# PIC24FJ64GB002_BT.net
KiCad netlist of a schematic drawn in EAGLE
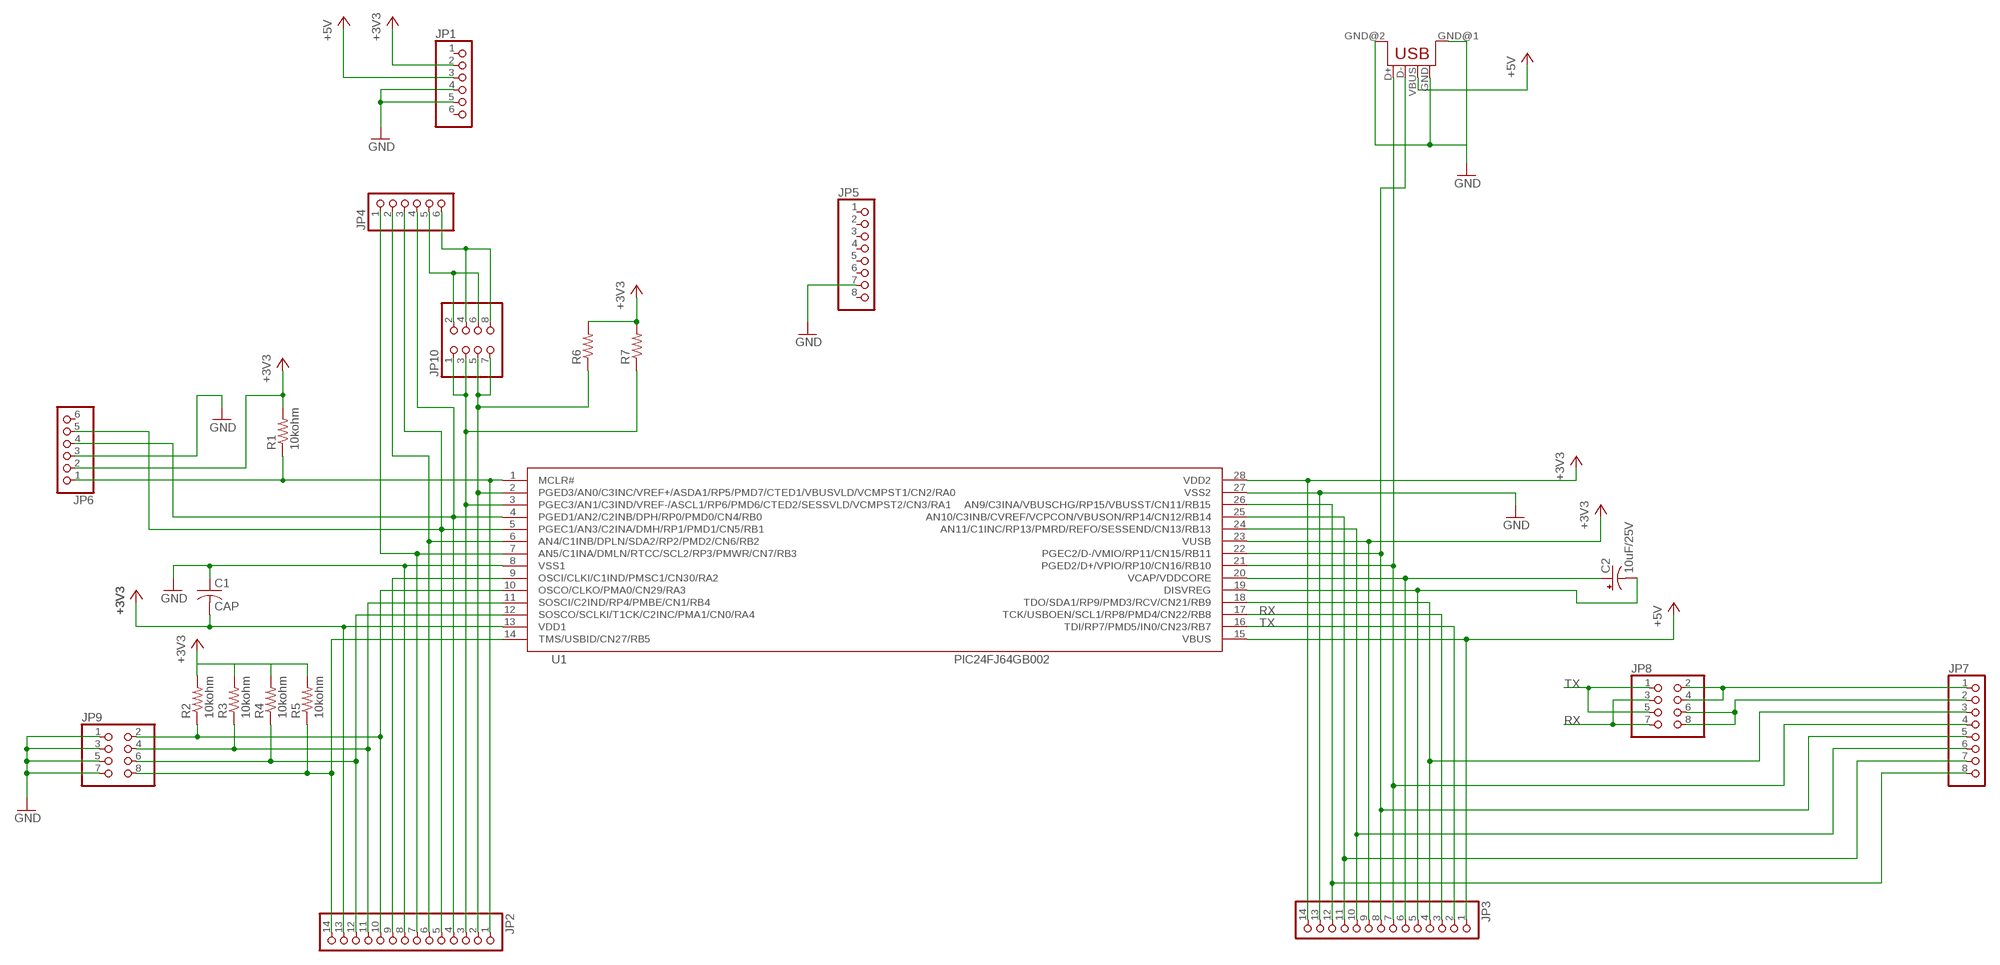
[diagram p0: schematic, sheet 1]

(export (version "E")
  (design (tool "Eeschema 10.0.6"))
  (components
    (comp (ref "C1")
      (value "CAP")
      (footprint "eagle-import:C025-040X050")
      (libsource (lib "eagle-import") (part "CAP"))
    )
    (comp (ref "C2")
      (value "10uF/25V")
      (footprint "eagle-import:CPOL-US")
      (libsource (lib "eagle-import") (part "CPOL-US"))
    )
    (comp (ref "CON1")
      (value "USB")
      (footprint "eagle-import:USB-FEMALE-A-PTH")
      (libsource (lib "eagle-import") (part "USB"))
    )
    (comp (ref "JP1")
      (value "PINHD-1X6")
      (footprint "eagle-import:1X06")
      (libsource (lib "eagle-import") (part "PINHD-1X6"))
    )
    (comp (ref "JP2")
      (value "PINHD-1X14")
      (footprint "eagle-import:1X14")
      (libsource (lib "eagle-import") (part "PINHD-1X14"))
    )
    (comp (ref "JP3")
      (value "PINHD-1X14")
      (footprint "eagle-import:1X14")
      (libsource (lib "eagle-import") (part "PINHD-1X14"))
    )
    (comp (ref "JP4")
      (value "PINHD-1X6")
      (footprint "eagle-import:1X06")
      (libsource (lib "eagle-import") (part "PINHD-1X6"))
    )
    (comp (ref "JP5")
      (value "PINHD-1X8")
      (footprint "eagle-import:1X08")
      (libsource (lib "eagle-import") (part "PINHD-1X8"))
    )
    (comp (ref "JP6")
      (value "PINHD-1X6")
      (footprint "eagle-import:1X06")
      (libsource (lib "eagle-import") (part "PINHD-1X6"))
    )
    (comp (ref "JP7")
      (value "PINHD-1X8")
      (footprint "eagle-import:1X08")
      (libsource (lib "eagle-import") (part "PINHD-1X8"))
    )
    (comp (ref "JP8")
      (value "PINHD-2X4")
      (footprint "eagle-import:2X04")
      (libsource (lib "eagle-import") (part "PINHD-2X4"))
    )
    (comp (ref "JP9")
      (value "PINHD-2X4")
      (footprint "eagle-import:2X04")
      (libsource (lib "eagle-import") (part "PINHD-2X4"))
    )
    (comp (ref "JP10")
      (value "PINHD-2X4")
      (footprint "eagle-import:2X04")
      (libsource (lib "eagle-import") (part "PINHD-2X4"))
    )
    (comp (ref "R1")
      (value "10kohm")
      (footprint "eagle-import:0204V")
      (libsource (lib "eagle-import") (part "R-US-01"))
    )
    (comp (ref "R2")
      (value "10kohm")
      (footprint "eagle-import:0204V")
      (libsource (lib "eagle-import") (part "R-US-01"))
    )
    (comp (ref "R3")
      (value "10kohm")
      (footprint "eagle-import:0204V")
      (libsource (lib "eagle-import") (part "R-US-01"))
    )
    (comp (ref "R4")
      (value "10kohm")
      (footprint "eagle-import:0204V")
      (libsource (lib "eagle-import") (part "R-US-01"))
    )
    (comp (ref "R5")
      (value "10kohm")
      (footprint "eagle-import:0204V")
      (libsource (lib "eagle-import") (part "R-US-01"))
    )
    (comp (ref "R6")
      (value "R-US-01")
      (footprint "eagle-import:0204V")
      (libsource (lib "eagle-import") (part "R-US-01"))
    )
    (comp (ref "R7")
      (value "R-US-01")
      (footprint "eagle-import:0204V")
      (libsource (lib "eagle-import") (part "R-US-01"))
    )
    (comp (ref "U1")
      (value "PIC24FJ64GB002")
      (footprint "eagle-import:DIP28")
      (libsource (lib "eagle-import") (part "PIC24FJ64GB002"))
    )
  )
  (nets
    (net (code "1") (name "+3V3") (class "Default")
      (node (ref "C1") (pin "2") (pinfunction "2_2") (pintype "passive"))
      (node (ref "JP1") (pin "2") (pinfunction "2_2") (pintype "passive"))
      (node (ref "JP2") (pin "13") (pinfunction "13_13") (pintype "passive"))
      (node (ref "JP3") (pin "14") (pinfunction "14_14") (pintype "passive"))
      (node (ref "JP3") (pin "9") (pinfunction "9_9") (pintype "passive"))
      (node (ref "JP6") (pin "2") (pinfunction "2_2") (pintype "passive"))
      (node (ref "R1") (pin "2") (pinfunction "2_2") (pintype "passive"))
      (node (ref "R2") (pin "2") (pinfunction "2_2") (pintype "passive"))
      (node (ref "R3") (pin "2") (pinfunction "2_2") (pintype "passive"))
      (node (ref "R4") (pin "2") (pinfunction "2_2") (pintype "passive"))
      (node (ref "R5") (pin "2") (pinfunction "2_2") (pintype "passive"))
      (node (ref "R6") (pin "2") (pinfunction "2_2") (pintype "passive"))
      (node (ref "R7") (pin "2") (pinfunction "2_2") (pintype "passive"))
      (node (ref "U1") (pin "13") (pinfunction "VDD1_13") (pintype "power_in"))
      (node (ref "U1") (pin "23") (pinfunction "VUSB_23") (pintype "power_in"))
      (node (ref "U1") (pin "28") (pinfunction "VDD2_28") (pintype "power_in"))
    )
    (net (code "2") (name "+5V") (class "Default")
      (node (ref "CON1") (pin "VBUS") (pinfunction "VBUS_VBUS") (pintype "bidirectional"))
      (node (ref "JP1") (pin "3") (pinfunction "3_3") (pintype "passive"))
      (node (ref "JP3") (pin "1") (pinfunction "1_1") (pintype "passive"))
      (node (ref "U1") (pin "15") (pinfunction "VBUS_15") (pintype "power_in"))
    )
    (net (code "3") (name "/RX") (class "Default")
      (node (ref "JP3") (pin "3") (pinfunction "3_3") (pintype "passive"))
      (node (ref "JP8") (pin "3") (pinfunction "3_3") (pintype "passive"))
      (node (ref "JP8") (pin "7") (pinfunction "7_7") (pintype "passive"))
      (node (ref "U1") (pin "17") (pinfunction "TCK/USBOEN/SCL1/RP8/PMD4/CN22/RB8_17") (pintype "bidirectional"))
    )
    (net (code "4") (name "/TX") (class "Default")
      (node (ref "JP3") (pin "2") (pinfunction "2_2") (pintype "passive"))
      (node (ref "JP8") (pin "1") (pinfunction "1_1") (pintype "passive"))
      (node (ref "JP8") (pin "5") (pinfunction "5_5") (pintype "passive"))
      (node (ref "U1") (pin "16") (pinfunction "TDI/RP7/PMD5/IN0/CN23/RB7_16") (pintype "bidirectional"))
    )
    (net (code "5") (name "GND") (class "Default")
      (node (ref "C1") (pin "1") (pinfunction "1_1") (pintype "passive"))
      (node (ref "CON1") (pin "GND") (pinfunction "GND_GND") (pintype "bidirectional"))
      (node (ref "CON1") (pin "GND@1") (pinfunction "GND_GND@1") (pintype "bidirectional"))
      (node (ref "CON1") (pin "GND@2") (pinfunction "GND_GND@2") (pintype "bidirectional"))
      (node (ref "JP1") (pin "4") (pinfunction "4_4") (pintype "passive"))
      (node (ref "JP1") (pin "5") (pinfunction "5_5") (pintype "passive"))
      (node (ref "JP2") (pin "8") (pinfunction "8_8") (pintype "passive"))
      (node (ref "JP3") (pin "13") (pinfunction "13_13") (pintype "passive"))
      (node (ref "JP5") (pin "7") (pinfunction "7_7") (pintype "passive"))
      (node (ref "JP6") (pin "3") (pinfunction "3_3") (pintype "passive"))
      (node (ref "JP9") (pin "1") (pinfunction "1_1") (pintype "passive"))
      (node (ref "JP9") (pin "3") (pinfunction "3_3") (pintype "passive"))
      (node (ref "JP9") (pin "5") (pinfunction "5_5") (pintype "passive"))
      (node (ref "JP9") (pin "7") (pinfunction "7_7") (pintype "passive"))
      (node (ref "U1") (pin "27") (pinfunction "VSS2_27") (pintype "power_in"))
      (node (ref "U1") (pin "8") (pinfunction "VSS1_8") (pintype "power_in"))
    )
    (net (code "6") (name "Net-(JP7-Pad1)") (class "Default")
      (node (ref "JP7") (pin "1") (pinfunction "1_1") (pintype "passive"))
      (node (ref "JP8") (pin "2") (pinfunction "2_2") (pintype "passive"))
      (node (ref "JP8") (pin "4") (pinfunction "4_4") (pintype "passive"))
    )
    (net (code "7") (name "Net-(JP7-Pad2)") (class "Default")
      (node (ref "JP7") (pin "2") (pinfunction "2_2") (pintype "passive"))
      (node (ref "JP8") (pin "6") (pinfunction "6_6") (pintype "passive"))
      (node (ref "JP8") (pin "8") (pinfunction "8_8") (pintype "passive"))
    )
    (net (code "8") (name "Net-(JP10-Pad2)") (class "Default")
      (node (ref "JP10") (pin "2") (pinfunction "2_2") (pintype "passive"))
      (node (ref "JP10") (pin "6") (pinfunction "6_6") (pintype "passive"))
      (node (ref "JP4") (pin "5") (pinfunction "5_5") (pintype "passive"))
    )
    (net (code "9") (name "Net-(JP10-Pad4)") (class "Default")
      (node (ref "JP10") (pin "4") (pinfunction "4_4") (pintype "passive"))
      (node (ref "JP10") (pin "8") (pinfunction "8_8") (pintype "passive"))
      (node (ref "JP4") (pin "6") (pinfunction "6_6") (pintype "passive"))
    )
    (net (code "10") (name "Net-(U1-AN4{slash}C1INB{slash}DPLN{slash}SDA2{slash}RP2{slash}PMD2{slash}CN6{slash}RB2)") (class "Default")
      (node (ref "JP2") (pin "6") (pinfunction "6_6") (pintype "passive"))
      (node (ref "JP4") (pin "2") (pinfunction "2_2") (pintype "passive"))
      (node (ref "U1") (pin "6") (pinfunction "AN4/C1INB/DPLN/SDA2/RP2/PMD2/CN6/RB2_6") (pintype "bidirectional"))
    )
    (net (code "11") (name "Net-(U1-AN5{slash}C1INA{slash}DMLN{slash}RTCC{slash}SCL2{slash}RP3{slash}PMWR{slash}CN7{slash}RB3)") (class "Default")
      (node (ref "JP2") (pin "7") (pinfunction "7_7") (pintype "passive"))
      (node (ref "JP4") (pin "1") (pinfunction "1_1") (pintype "passive"))
      (node (ref "U1") (pin "7") (pinfunction "AN5/C1INA/DMLN/RTCC/SCL2/RP3/PMWR/CN7/RB3_7") (pintype "bidirectional"))
    )
    (net (code "12") (name "Net-(U1-AN9{slash}C3INA{slash}VBUSCHG{slash}RP15{slash}VBUSST{slash}CN11{slash}RB15)") (class "Default")
      (node (ref "JP3") (pin "12") (pinfunction "12_12") (pintype "passive"))
      (node (ref "JP7") (pin "8") (pinfunction "8_8") (pintype "passive"))
      (node (ref "U1") (pin "26") (pinfunction "AN9/C3INA/VBUSCHG/RP15/VBUSST/CN11/RB15_26") (pintype "bidirectional"))
    )
    (net (code "13") (name "Net-(U1-AN10{slash}C3INB{slash}CVREF{slash}VCPCON{slash}VBUSON{slash}RP14{slash}CN12{slash}RB14)") (class "Default")
      (node (ref "JP3") (pin "11") (pinfunction "11_11") (pintype "passive"))
      (node (ref "JP7") (pin "7") (pinfunction "7_7") (pintype "passive"))
      (node (ref "U1") (pin "25") (pinfunction "AN10/C3INB/CVREF/VCPCON/VBUSON/RP14/CN12/RB14_25") (pintype "bidirectional"))
    )
    (net (code "14") (name "Net-(U1-AN11{slash}C1INC{slash}RP13{slash}PMRD{slash}REFO{slash}SESSEND{slash}CN13{slash}RB13)") (class "Default")
      (node (ref "JP3") (pin "10") (pinfunction "10_10") (pintype "passive"))
      (node (ref "JP7") (pin "6") (pinfunction "6_6") (pintype "passive"))
      (node (ref "U1") (pin "24") (pinfunction "AN11/C1INC/RP13/PMRD/REFO/SESSEND/CN13/RB13_24") (pintype "bidirectional"))
    )
    (net (code "15") (name "Net-(U1-DISVREG)") (class "Default")
      (node (ref "C2") (pin "-") (pinfunction "-_-") (pintype "passive"))
      (node (ref "JP3") (pin "5") (pinfunction "5_5") (pintype "passive"))
      (node (ref "U1") (pin "19") (pinfunction "DISVREG_19") (pintype "power_in"))
    )
    (net (code "16") (name "Net-(U1-MCLR#)") (class "Default")
      (node (ref "JP2") (pin "1") (pinfunction "1_1") (pintype "passive"))
      (node (ref "JP6") (pin "1") (pinfunction "1_1") (pintype "passive"))
      (node (ref "R1") (pin "1") (pinfunction "1_1") (pintype "passive"))
      (node (ref "U1") (pin "1") (pinfunction "MCLR#_1") (pintype "bidirectional"))
    )
    (net (code "17") (name "Net-(U1-OSCI{slash}CLKI{slash}C1IND{slash}PMSC1{slash}CN30{slash}RA2)") (class "Default")
      (node (ref "JP2") (pin "9") (pinfunction "9_9") (pintype "passive"))
      (node (ref "U1") (pin "9") (pinfunction "OSCI/CLKI/C1IND/PMSC1/CN30/RA2_9") (pintype "bidirectional"))
    )
    (net (code "18") (name "Net-(U1-OSCO{slash}CLKO{slash}PMA0{slash}CN29{slash}RA3)") (class "Default")
      (node (ref "JP2") (pin "10") (pinfunction "10_10") (pintype "passive"))
      (node (ref "JP9") (pin "2") (pinfunction "2_2") (pintype "passive"))
      (node (ref "R2") (pin "1") (pinfunction "1_1") (pintype "passive"))
      (node (ref "U1") (pin "10") (pinfunction "OSCO/CLKO/PMA0/CN29/RA3_10") (pintype "bidirectional"))
    )
    (net (code "19") (name "Net-(U1-PGEC1{slash}AN3{slash}C2INA{slash}DMH{slash}RP1{slash}PMD1{slash}CN5{slash}RB1)") (class "Default")
      (node (ref "JP2") (pin "5") (pinfunction "5_5") (pintype "passive"))
      (node (ref "JP4") (pin "3") (pinfunction "3_3") (pintype "passive"))
      (node (ref "JP6") (pin "5") (pinfunction "5_5") (pintype "passive"))
      (node (ref "U1") (pin "5") (pinfunction "PGEC1/AN3/C2INA/DMH/RP1/PMD1/CN5/RB1_5") (pintype "bidirectional"))
    )
    (net (code "20") (name "Net-(U1-PGEC2{slash}D-{slash}VMIO{slash}RP11{slash}CN15{slash}RB11)") (class "Default")
      (node (ref "CON1") (pin "D-") (pinfunction "D-_D-") (pintype "bidirectional"))
      (node (ref "JP3") (pin "8") (pinfunction "8_8") (pintype "passive"))
      (node (ref "JP7") (pin "5") (pinfunction "5_5") (pintype "passive"))
      (node (ref "U1") (pin "22") (pinfunction "PGEC2/D-/VMIO/RP11/CN15/RB11_22") (pintype "bidirectional"))
    )
    (net (code "21") (name "Net-(U1-PGEC3{slash}AN1{slash}C3IND{slash}VREF-{slash}ASCL1{slash}RP6{slash}PMD6{slash}CTED2{slash}SESSVLD{slash}VCMPST2{slash}CN3{slash}RA1)") (class "Default")
      (node (ref "JP10") (pin "1") (pinfunction "1_1") (pintype "passive"))
      (node (ref "JP10") (pin "3") (pinfunction "3_3") (pintype "passive"))
      (node (ref "JP2") (pin "3") (pinfunction "3_3") (pintype "passive"))
      (node (ref "R7") (pin "1") (pinfunction "1_1") (pintype "passive"))
      (node (ref "U1") (pin "3") (pinfunction "PGEC3/AN1/C3IND/VREF-/ASCL1/RP6/PMD6/CTED2/SESSVLD/VCMPST2/CN3/RA1_3") (pintype "bidirectional"))
    )
    (net (code "22") (name "Net-(U1-PGED1{slash}AN2{slash}C2INB{slash}DPH{slash}RP0{slash}PMD0{slash}CN4{slash}RB0)") (class "Default")
      (node (ref "JP2") (pin "4") (pinfunction "4_4") (pintype "passive"))
      (node (ref "JP4") (pin "4") (pinfunction "4_4") (pintype "passive"))
      (node (ref "JP6") (pin "4") (pinfunction "4_4") (pintype "passive"))
      (node (ref "U1") (pin "4") (pinfunction "PGED1/AN2/C2INB/DPH/RP0/PMD0/CN4/RB0_4") (pintype "bidirectional"))
    )
    (net (code "23") (name "Net-(U1-PGED2{slash}D+{slash}VPIO{slash}RP10{slash}CN16{slash}RB10)") (class "Default")
      (node (ref "CON1") (pin "D+") (pinfunction "D+_D+") (pintype "bidirectional"))
      (node (ref "JP3") (pin "7") (pinfunction "7_7") (pintype "passive"))
      (node (ref "JP7") (pin "4") (pinfunction "4_4") (pintype "passive"))
      (node (ref "U1") (pin "21") (pinfunction "PGED2/D+/VPIO/RP10/CN16/RB10_21") (pintype "bidirectional"))
    )
    (net (code "24") (name "Net-(U1-PGED3{slash}AN0{slash}C3INC{slash}VREF+{slash}ASDA1{slash}RP5{slash}PMD7{slash}CTED1{slash}VBUSVLD{slash}VCMPST1{slash}CN2{slash}RA0)") (class "Default")
      (node (ref "JP10") (pin "5") (pinfunction "5_5") (pintype "passive"))
      (node (ref "JP10") (pin "7") (pinfunction "7_7") (pintype "passive"))
      (node (ref "JP2") (pin "2") (pinfunction "2_2") (pintype "passive"))
      (node (ref "R6") (pin "1") (pinfunction "1_1") (pintype "passive"))
      (node (ref "U1") (pin "2") (pinfunction "PGED3/AN0/C3INC/VREF+/ASDA1/RP5/PMD7/CTED1/VBUSVLD/VCMPST1/CN2/RA0_2") (pintype "bidirectional"))
    )
    (net (code "25") (name "Net-(U1-SOSCI{slash}C2IND{slash}RP4{slash}PMBE{slash}CN1{slash}RB4)") (class "Default")
      (node (ref "JP2") (pin "11") (pinfunction "11_11") (pintype "passive"))
      (node (ref "JP9") (pin "4") (pinfunction "4_4") (pintype "passive"))
      (node (ref "R3") (pin "1") (pinfunction "1_1") (pintype "passive"))
      (node (ref "U1") (pin "11") (pinfunction "SOSCI/C2IND/RP4/PMBE/CN1/RB4_11") (pintype "bidirectional"))
    )
    (net (code "26") (name "Net-(U1-SOSCO{slash}SCLKI{slash}T1CK{slash}C2INC{slash}PMA1{slash}CN0{slash}RA4)") (class "Default")
      (node (ref "JP2") (pin "12") (pinfunction "12_12") (pintype "passive"))
      (node (ref "JP9") (pin "6") (pinfunction "6_6") (pintype "passive"))
      (node (ref "R4") (pin "1") (pinfunction "1_1") (pintype "passive"))
      (node (ref "U1") (pin "12") (pinfunction "SOSCO/SCLKI/T1CK/C2INC/PMA1/CN0/RA4_12") (pintype "bidirectional"))
    )
    (net (code "27") (name "Net-(U1-TDO{slash}SDA1{slash}RP9{slash}PMD3{slash}RCV{slash}CN21{slash}RB9)") (class "Default")
      (node (ref "JP3") (pin "4") (pinfunction "4_4") (pintype "passive"))
      (node (ref "JP7") (pin "3") (pinfunction "3_3") (pintype "passive"))
      (node (ref "U1") (pin "18") (pinfunction "TDO/SDA1/RP9/PMD3/RCV/CN21/RB9_18") (pintype "bidirectional"))
    )
    (net (code "28") (name "Net-(U1-TMS{slash}USBID{slash}CN27{slash}RB5)") (class "Default")
      (node (ref "JP2") (pin "14") (pinfunction "14_14") (pintype "passive"))
      (node (ref "JP9") (pin "8") (pinfunction "8_8") (pintype "passive"))
      (node (ref "R5") (pin "1") (pinfunction "1_1") (pintype "passive"))
      (node (ref "U1") (pin "14") (pinfunction "TMS/USBID/CN27/RB5_14") (pintype "bidirectional"))
    )
    (net (code "29") (name "Net-(U1-VCAP{slash}VDDCORE)") (class "Default")
      (node (ref "C2") (pin "+") (pinfunction "+_+") (pintype "passive"))
      (node (ref "JP3") (pin "6") (pinfunction "6_6") (pintype "passive"))
      (node (ref "U1") (pin "20") (pinfunction "VCAP/VDDCORE_20") (pintype "power_in"))
    )
    (net (code "30") (name "unconnected-(JP1-Pad1)") (class "Default")
      (node (ref "JP1") (pin "1") (pinfunction "1_1") (pintype "passive"))
    )
    (net (code "31") (name "unconnected-(JP1-Pad6)") (class "Default")
      (node (ref "JP1") (pin "6") (pinfunction "6_6") (pintype "passive"))
    )
    (net (code "32") (name "unconnected-(JP5-Pad1)") (class "Default")
      (node (ref "JP5") (pin "1") (pinfunction "1_1") (pintype "passive"))
    )
    (net (code "33") (name "unconnected-(JP5-Pad2)") (class "Default")
      (node (ref "JP5") (pin "2") (pinfunction "2_2") (pintype "passive"))
    )
    (net (code "34") (name "unconnected-(JP5-Pad3)") (class "Default")
      (node (ref "JP5") (pin "3") (pinfunction "3_3") (pintype "passive"))
    )
    (net (code "35") (name "unconnected-(JP5-Pad4)") (class "Default")
      (node (ref "JP5") (pin "4") (pinfunction "4_4") (pintype "passive"))
    )
    (net (code "36") (name "unconnected-(JP5-Pad5)") (class "Default")
      (node (ref "JP5") (pin "5") (pinfunction "5_5") (pintype "passive"))
    )
    (net (code "37") (name "unconnected-(JP5-Pad6)") (class "Default")
      (node (ref "JP5") (pin "6") (pinfunction "6_6") (pintype "passive"))
    )
    (net (code "38") (name "unconnected-(JP5-Pad8)") (class "Default")
      (node (ref "JP5") (pin "8") (pinfunction "8_8") (pintype "passive"))
    )
    (net (code "39") (name "unconnected-(JP6-Pad6)") (class "Default")
      (node (ref "JP6") (pin "6") (pinfunction "6_6") (pintype "passive"))
    )
  )
)
